# RAM_Module.net
KiCad netlist of a schematic drawn in Altium Designer
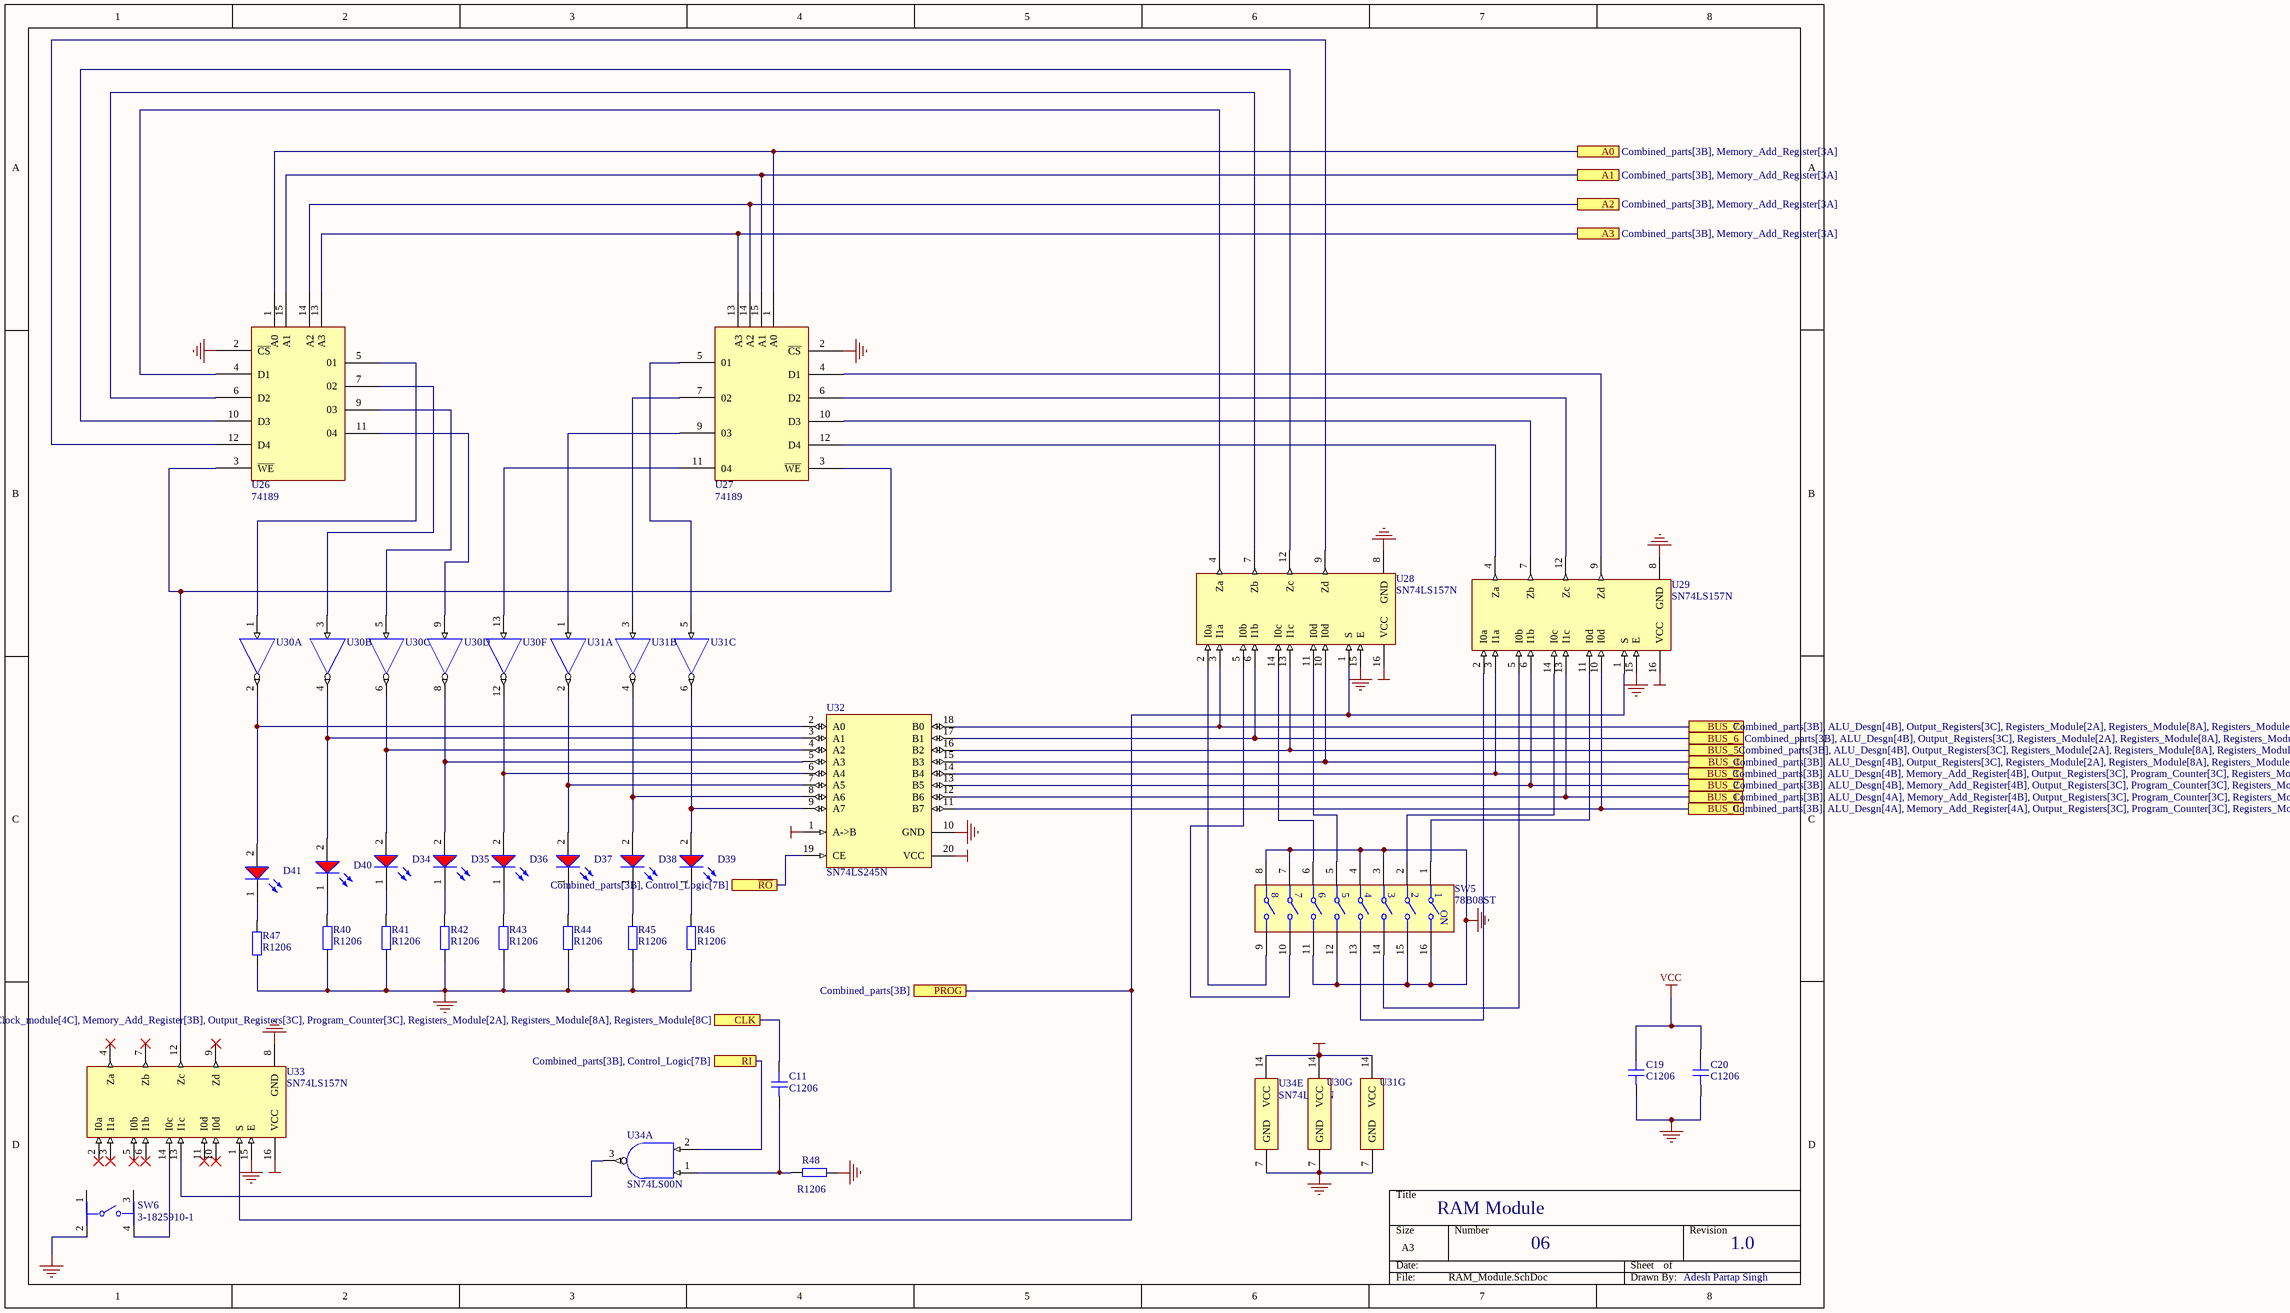
[diagram p0: RAM_Module.SchDoc]

(export (version "E")
  (design (tool "Eeschema 10.0.6"))
  (components
    (comp (ref "C11")
      (value "C1206")
      (footprint "CAP_1206")
      (description "Capacitor SMD 1206")
      (libsource (lib "Schematic-Lib-PhilsLab") (part "CAP_1206"))
    )
    (comp (ref "C19")
      (value "C1206")
      (footprint "CAP_1206")
      (description "Capacitor SMD 1206")
      (libsource (lib "Schematic-Lib-PhilsLab") (part "CAP_1206"))
    )
    (comp (ref "C20")
      (value "C1206")
      (footprint "CAP_1206")
      (description "Capacitor SMD 1206")
      (libsource (lib "Schematic-Lib-PhilsLab") (part "CAP_1206"))
    )
    (comp (ref "D34")
      (value "151053RS03000")
      (footprint "WL-TMRW_D5.8H11.7")
      (libsource (lib "8BIT_COMP_LIB") (part "CMP-1489-00007-2"))
    )
    (comp (ref "D35")
      (value "151053RS03000")
      (footprint "WL-TMRW_D5.8H11.7")
      (libsource (lib "8BIT_COMP_LIB") (part "CMP-1489-00007-2"))
    )
    (comp (ref "D36")
      (value "151053RS03000")
      (footprint "WL-TMRW_D5.8H11.7")
      (libsource (lib "8BIT_COMP_LIB") (part "CMP-1489-00007-2"))
    )
    (comp (ref "D37")
      (value "151053RS03000")
      (footprint "WL-TMRW_D5.8H11.7")
      (libsource (lib "8BIT_COMP_LIB") (part "CMP-1489-00007-2"))
    )
    (comp (ref "D38")
      (value "151053RS03000")
      (footprint "WL-TMRW_D5.8H11.7")
      (libsource (lib "8BIT_COMP_LIB") (part "CMP-1489-00007-2"))
    )
    (comp (ref "D39")
      (value "151053RS03000")
      (footprint "WL-TMRW_D5.8H11.7")
      (libsource (lib "8BIT_COMP_LIB") (part "CMP-1489-00007-2"))
    )
    (comp (ref "D40")
      (value "151053RS03000")
      (footprint "WL-TMRW_D5.8H11.7")
      (libsource (lib "8BIT_COMP_LIB") (part "CMP-1489-00007-2"))
    )
    (comp (ref "D41")
      (value "151053RS03000")
      (footprint "WL-TMRW_D5.8H11.7")
      (libsource (lib "8BIT_COMP_LIB") (part "CMP-1489-00007-2"))
    )
    (comp (ref "R40")
      (value "R1206")
      (footprint "RES_1206")
      (description "Resistor SMD 1206")
      (libsource (lib "Schematic-Lib-PhilsLab") (part "RES_1206"))
    )
    (comp (ref "R41")
      (value "R1206")
      (footprint "RES_1206")
      (description "Resistor SMD 1206")
      (libsource (lib "Schematic-Lib-PhilsLab") (part "RES_1206"))
    )
    (comp (ref "R42")
      (value "R1206")
      (footprint "RES_1206")
      (description "Resistor SMD 1206")
      (libsource (lib "Schematic-Lib-PhilsLab") (part "RES_1206"))
    )
    (comp (ref "R43")
      (value "R1206")
      (footprint "RES_1206")
      (description "Resistor SMD 1206")
      (libsource (lib "Schematic-Lib-PhilsLab") (part "RES_1206"))
    )
    (comp (ref "R44")
      (value "R1206")
      (footprint "RES_1206")
      (description "Resistor SMD 1206")
      (libsource (lib "Schematic-Lib-PhilsLab") (part "RES_1206"))
    )
    (comp (ref "R45")
      (value "R1206")
      (footprint "RES_1206")
      (description "Resistor SMD 1206")
      (libsource (lib "Schematic-Lib-PhilsLab") (part "RES_1206"))
    )
    (comp (ref "R46")
      (value "R1206")
      (footprint "RES_1206")
      (description "Resistor SMD 1206")
      (libsource (lib "Schematic-Lib-PhilsLab") (part "RES_1206"))
    )
    (comp (ref "R47")
      (value "R1206")
      (footprint "RES_1206")
      (description "Resistor SMD 1206")
      (libsource (lib "Schematic-Lib-PhilsLab") (part "RES_1206"))
    )
    (comp (ref "R48")
      (value "R1206")
      (footprint "RES_1206")
      (description "Resistor SMD 1206")
      (libsource (lib "Schematic-Lib-PhilsLab") (part "RES_1206"))
    )
    (comp (ref "SW5")
      (value "78B08ST")
      (footprint "FP-78B08ST-MFG")
      (description "SWITCH SLIDE DIP SPST 150MA 30V")
      (libsource (lib "8BIT_COMP_LIB") (part "CMP-31942-000004-2"))
    )
    (comp (ref "SW6")
      (value "3-1825910-1")
      (footprint "FP-3-1825910-1-MFG")
      (description "SWITCH TACTILE SPST-NO 0.05A 24V")
      (fields
        (field (name "MANUFACTURER") "TE Connectivity")
        (field (name "OCTOPART") "https://octopart.com/3-1825910-1-te+connectivity-46506874")
      )
      (libsource (lib "8BIT_COMP_LIB") (part "CMP-03407-000001-1"))
    )
    (comp (ref "U26")
      (value "74189")
      (footprint "N0016A")
      (description "RAM")
      (fields
        (field (name "MANUFACTURER") "Texas Instruments")
        (field (name "GENERIC PART NUMBER") "SN74LS157")
      )
      (libsource (lib "8BIT_COMP_LIB") (part "64 BIT RAM"))
    )
    (comp (ref "U27")
      (value "74189")
      (footprint "N0016A")
      (description "RAM")
      (fields
        (field (name "MANUFACTURER") "Texas Instruments")
        (field (name "GENERIC PART NUMBER") "SN74LS157")
      )
      (libsource (lib "8BIT_COMP_LIB") (part "64 BIT RAM_2"))
    )
    (comp (ref "U28")
      (value "SN74LS157N")
      (footprint "N0016A")
      (description "Quadruple 2-Line To 1-Line Data Selectors/Multiplexers, N0016A, TUBE")
      (fields
        (field (name "MANUFACTURER") "Texas Instruments")
        (field (name "GENERIC PART NUMBER") "SN74LS157")
      )
      (libsource (lib "8BIT_COMP_LIB") (part "CMP-1633-00683-2"))
    )
    (comp (ref "U29")
      (value "SN74LS157N")
      (footprint "N0016A")
      (description "Quadruple 2-Line To 1-Line Data Selectors/Multiplexers, N0016A, TUBE")
      (fields
        (field (name "MANUFACTURER") "Texas Instruments")
        (field (name "GENERIC PART NUMBER") "SN74LS157")
      )
      (libsource (lib "8BIT_COMP_LIB") (part "CMP-1633-00683-2"))
    )
    (comp (ref "U30")
      (value "SN74LS04NSR")
      (footprint "NS0014A_M")
      (description "Hex inverters, NS0014A, LARGE T&R")
      (fields
        (field (name "MANUFACTURER") "Texas Instruments")
        (field (name "GENERIC PART NUMBER") "SN74LS04")
      )
      (libsource (lib "8BIT_COMP_LIB") (part "CMP-1615-00958-3"))
    )
    (comp (ref "U31")
      (value "SN74LS04NSR")
      (footprint "NS0014A_M")
      (description "Hex inverters, NS0014A, LARGE T&R")
      (fields
        (field (name "MANUFACTURER") "Texas Instruments")
        (field (name "GENERIC PART NUMBER") "SN74LS04")
      )
      (libsource (lib "8BIT_COMP_LIB") (part "CMP-1615-00958-3"))
    )
    (comp (ref "U32")
      (value "SN74LS245N")
      (footprint "FP-N0020A-MFG")
      (description "IC TXRX NON-INVERT 5.25V 20DIP")
      (libsource (lib "8BIT_COMP_LIB") (part "CMP-1620-00419-3"))
    )
    (comp (ref "U33")
      (value "SN74LS157N")
      (footprint "N0016A")
      (description "Quadruple 2-Line To 1-Line Data Selectors/Multiplexers, N0016A, TUBE")
      (fields
        (field (name "MANUFACTURER") "Texas Instruments")
        (field (name "GENERIC PART NUMBER") "SN74LS157")
      )
      (libsource (lib "8BIT_COMP_LIB") (part "CMP-1633-00683-2"))
    )
    (comp (ref "U34")
      (value "SN74LS00N")
      (footprint "N0014A")
      (description "Quad 2-input positive-NAND gates, N0014A, TUBE")
      (fields
        (field (name "MANUFACTURER") "Texas Instruments")
        (field (name "GENERIC PART NUMBER") "SN74LS00")
      )
      (libsource (lib "") (part "CMP-1627-00476-2_1"))
    )
  )
  (nets
    (net (code "1") (name "/A0") (class "Default")
      (node (ref "U26") (pin "1") (pinfunction "A0_1") (pintype "passive"))
      (node (ref "U27") (pin "1") (pinfunction "A0_1") (pintype "passive"))
    )
    (net (code "2") (name "/A1") (class "Default")
      (node (ref "U26") (pin "15") (pinfunction "A1_15") (pintype "passive"))
      (node (ref "U27") (pin "15") (pinfunction "A1_15") (pintype "passive"))
    )
    (net (code "3") (name "/A2") (class "Default")
      (node (ref "U26") (pin "14") (pinfunction "A2_14") (pintype "passive"))
      (node (ref "U27") (pin "14") (pinfunction "A2_14") (pintype "passive"))
    )
    (net (code "4") (name "/A3") (class "Default")
      (node (ref "U26") (pin "13") (pinfunction "A3_13") (pintype "passive"))
      (node (ref "U27") (pin "13") (pinfunction "A3_13") (pintype "passive"))
    )
    (net (code "5") (name "/BUS_0") (class "Default")
      (node (ref "U29") (pin "10") (pinfunction "I0d_10") (pintype "input"))
      (node (ref "U32") (pin "11") (pinfunction "B7_11") (pintype "bidirectional"))
    )
    (net (code "6") (name "/BUS_1") (class "Default")
      (node (ref "U29") (pin "13") (pinfunction "I1c_13") (pintype "input"))
      (node (ref "U32") (pin "12") (pinfunction "B6_12") (pintype "bidirectional"))
    )
    (net (code "7") (name "/BUS_2") (class "Default")
      (node (ref "U29") (pin "6") (pinfunction "I1b_6") (pintype "input"))
      (node (ref "U32") (pin "13") (pinfunction "B5_13") (pintype "bidirectional"))
    )
    (net (code "8") (name "/BUS_3") (class "Default")
      (node (ref "U29") (pin "3") (pinfunction "I1a_3") (pintype "input"))
      (node (ref "U32") (pin "14") (pinfunction "B4_14") (pintype "bidirectional"))
    )
    (net (code "9") (name "/BUS_4") (class "Default")
      (node (ref "U28") (pin "10") (pinfunction "I0d_10") (pintype "input"))
      (node (ref "U32") (pin "15") (pinfunction "B3_15") (pintype "bidirectional"))
    )
    (net (code "10") (name "/BUS_5") (class "Default")
      (node (ref "U28") (pin "13") (pinfunction "I1c_13") (pintype "input"))
      (node (ref "U32") (pin "16") (pinfunction "B2_16") (pintype "bidirectional"))
    )
    (net (code "11") (name "/BUS_6") (class "Default")
      (node (ref "U28") (pin "6") (pinfunction "I1b_6") (pintype "input"))
      (node (ref "U32") (pin "17") (pinfunction "B1_17") (pintype "bidirectional"))
    )
    (net (code "12") (name "/BUS_7") (class "Default")
      (node (ref "U28") (pin "3") (pinfunction "I1a_3") (pintype "input"))
      (node (ref "U32") (pin "18") (pinfunction "B0_18") (pintype "bidirectional"))
    )
    (net (code "13") (name "/CLK") (class "Default")
      (node (ref "C11") (pin "2") (pinfunction "2_2") (pintype "passive"))
    )
    (net (code "14") (name "/PROG") (class "Default")
      (node (ref "U28") (pin "1") (pinfunction "S_1") (pintype "input"))
      (node (ref "U29") (pin "1") (pinfunction "S_1") (pintype "input"))
      (node (ref "U33") (pin "1") (pinfunction "S_1") (pintype "input"))
    )
    (net (code "15") (name "/RI") (class "Default")
      (node (ref "U34") (pin "2") (pinfunction "1B_2") (pintype "input"))
    )
    (net (code "16") (name "/~{RO}") (class "Default")
      (node (ref "U32") (pin "19") (pinfunction "CE_19") (pintype "input"))
    )
    (net (code "17") (name "GND") (class "Default")
      (node (ref "C19") (pin "1") (pinfunction "1_1") (pintype "passive"))
      (node (ref "C20") (pin "1") (pinfunction "1_1") (pintype "passive"))
      (node (ref "R40") (pin "1") (pinfunction "1_1") (pintype "passive"))
      (node (ref "R41") (pin "1") (pinfunction "1_1") (pintype "passive"))
      (node (ref "R42") (pin "1") (pinfunction "1_1") (pintype "passive"))
      (node (ref "R43") (pin "1") (pinfunction "1_1") (pintype "passive"))
      (node (ref "R44") (pin "1") (pinfunction "1_1") (pintype "passive"))
      (node (ref "R45") (pin "1") (pinfunction "1_1") (pintype "passive"))
      (node (ref "R46") (pin "1") (pinfunction "1_1") (pintype "passive"))
      (node (ref "R47") (pin "1") (pinfunction "1_1") (pintype "passive"))
      (node (ref "R48") (pin "1") (pinfunction "1_1") (pintype "passive"))
      (node (ref "SW5") (pin "11") (pinfunction "11_11") (pintype "passive"))
      (node (ref "SW5") (pin "12") (pinfunction "12_12") (pintype "passive"))
      (node (ref "SW5") (pin "15") (pinfunction "15_15") (pintype "passive"))
      (node (ref "SW5") (pin "16") (pinfunction "16_16") (pintype "passive"))
      (node (ref "SW5") (pin "3") (pinfunction "3_3") (pintype "passive"))
      (node (ref "SW5") (pin "4") (pinfunction "4_4") (pintype "passive"))
      (node (ref "SW5") (pin "7") (pinfunction "7_7") (pintype "passive"))
      (node (ref "SW5") (pin "8") (pinfunction "8_8") (pintype "passive"))
      (node (ref "SW6") (pin "2") (pinfunction "2_2") (pintype "passive"))
      (node (ref "U26") (pin "2") (pinfunction "~{CS}_2") (pintype "passive"))
      (node (ref "U27") (pin "2") (pinfunction "~{CS}_2") (pintype "passive"))
      (node (ref "U28") (pin "15") (pinfunction "E_15") (pintype "input"))
      (node (ref "U28") (pin "8") (pinfunction "GND_8") (pintype "power_in"))
      (node (ref "U29") (pin "15") (pinfunction "E_15") (pintype "input"))
      (node (ref "U29") (pin "8") (pinfunction "GND_8") (pintype "power_in"))
      (node (ref "U30") (pin "7") (pinfunction "GND_7") (pintype "power_in"))
      (node (ref "U31") (pin "7") (pinfunction "GND_7") (pintype "power_in"))
      (node (ref "U32") (pin "10") (pinfunction "GND_10") (pintype "power_in"))
      (node (ref "U33") (pin "15") (pinfunction "E_15") (pintype "input"))
      (node (ref "U33") (pin "8") (pinfunction "GND_8") (pintype "power_in"))
      (node (ref "U34") (pin "7") (pinfunction "GND_7") (pintype "power_in"))
    )
    (net (code "18") (name "Net-(D34-A)") (class "Default")
      (node (ref "D34") (pin "2") (pinfunction "A_2") (pintype "passive"))
      (node (ref "U30") (pin "6") (pinfunction "~{3Y}_6") (pintype "output"))
      (node (ref "U32") (pin "4") (pinfunction "A2_4") (pintype "bidirectional"))
    )
    (net (code "19") (name "Net-(D34-K)") (class "Default")
      (node (ref "D34") (pin "1") (pinfunction "K_1") (pintype "passive"))
      (node (ref "R41") (pin "2") (pinfunction "2_2") (pintype "passive"))
    )
    (net (code "20") (name "Net-(D35-A)") (class "Default")
      (node (ref "D35") (pin "2") (pinfunction "A_2") (pintype "passive"))
      (node (ref "U30") (pin "8") (pinfunction "~{4Y}_8") (pintype "output"))
      (node (ref "U32") (pin "5") (pinfunction "A3_5") (pintype "bidirectional"))
    )
    (net (code "21") (name "Net-(D35-K)") (class "Default")
      (node (ref "D35") (pin "1") (pinfunction "K_1") (pintype "passive"))
      (node (ref "R42") (pin "2") (pinfunction "2_2") (pintype "passive"))
    )
    (net (code "22") (name "Net-(D36-A)") (class "Default")
      (node (ref "D36") (pin "2") (pinfunction "A_2") (pintype "passive"))
      (node (ref "U30") (pin "12") (pinfunction "~{6Y}_12") (pintype "output"))
      (node (ref "U32") (pin "6") (pinfunction "A4_6") (pintype "bidirectional"))
    )
    (net (code "23") (name "Net-(D36-K)") (class "Default")
      (node (ref "D36") (pin "1") (pinfunction "K_1") (pintype "passive"))
      (node (ref "R43") (pin "2") (pinfunction "2_2") (pintype "passive"))
    )
    (net (code "24") (name "Net-(D37-A)") (class "Default")
      (node (ref "D37") (pin "2") (pinfunction "A_2") (pintype "passive"))
      (node (ref "U31") (pin "2") (pinfunction "~{1Y}_2") (pintype "output"))
      (node (ref "U32") (pin "7") (pinfunction "A5_7") (pintype "bidirectional"))
    )
    (net (code "25") (name "Net-(D37-K)") (class "Default")
      (node (ref "D37") (pin "1") (pinfunction "K_1") (pintype "passive"))
      (node (ref "R44") (pin "2") (pinfunction "2_2") (pintype "passive"))
    )
    (net (code "26") (name "Net-(D38-A)") (class "Default")
      (node (ref "D38") (pin "2") (pinfunction "A_2") (pintype "passive"))
      (node (ref "U31") (pin "4") (pinfunction "~{2Y}_4") (pintype "output"))
      (node (ref "U32") (pin "8") (pinfunction "A6_8") (pintype "bidirectional"))
    )
    (net (code "27") (name "Net-(D38-K)") (class "Default")
      (node (ref "D38") (pin "1") (pinfunction "K_1") (pintype "passive"))
      (node (ref "R45") (pin "2") (pinfunction "2_2") (pintype "passive"))
    )
    (net (code "28") (name "Net-(D39-A)") (class "Default")
      (node (ref "D39") (pin "2") (pinfunction "A_2") (pintype "passive"))
      (node (ref "U31") (pin "6") (pinfunction "~{3Y}_6") (pintype "output"))
      (node (ref "U32") (pin "9") (pinfunction "A7_9") (pintype "bidirectional"))
    )
    (net (code "29") (name "Net-(D39-K)") (class "Default")
      (node (ref "D39") (pin "1") (pinfunction "K_1") (pintype "passive"))
      (node (ref "R46") (pin "2") (pinfunction "2_2") (pintype "passive"))
    )
    (net (code "30") (name "Net-(D40-A)") (class "Default")
      (node (ref "D40") (pin "2") (pinfunction "A_2") (pintype "passive"))
      (node (ref "U30") (pin "4") (pinfunction "~{2Y}_4") (pintype "output"))
      (node (ref "U32") (pin "3") (pinfunction "A1_3") (pintype "bidirectional"))
    )
    (net (code "31") (name "Net-(D40-K)") (class "Default")
      (node (ref "D40") (pin "1") (pinfunction "K_1") (pintype "passive"))
      (node (ref "R40") (pin "2") (pinfunction "2_2") (pintype "passive"))
    )
    (net (code "32") (name "Net-(D41-A)") (class "Default")
      (node (ref "D41") (pin "2") (pinfunction "A_2") (pintype "passive"))
      (node (ref "U30") (pin "2") (pinfunction "~{1Y}_2") (pintype "output"))
      (node (ref "U32") (pin "2") (pinfunction "A0_2") (pintype "bidirectional"))
    )
    (net (code "33") (name "Net-(D41-K)") (class "Default")
      (node (ref "D41") (pin "1") (pinfunction "K_1") (pintype "passive"))
      (node (ref "R47") (pin "2") (pinfunction "2_2") (pintype "passive"))
    )
    (net (code "34") (name "Net-(SW5-Pad1)") (class "Default")
      (node (ref "SW5") (pin "1") (pinfunction "1_1") (pintype "passive"))
      (node (ref "U29") (pin "11") (pinfunction "I0d_11") (pintype "input"))
    )
    (net (code "35") (name "Net-(SW5-Pad5)") (class "Default")
      (node (ref "SW5") (pin "5") (pinfunction "5_5") (pintype "passive"))
      (node (ref "U28") (pin "11") (pinfunction "I0d_11") (pintype "input"))
    )
    (net (code "36") (name "Net-(U26-01)") (class "Default")
      (node (ref "U26") (pin "5") (pinfunction "01_5") (pintype "passive"))
      (node (ref "U30") (pin "1") (pinfunction "1A_1") (pintype "input"))
    )
    (net (code "37") (name "Net-(U26-02)") (class "Default")
      (node (ref "U26") (pin "7") (pinfunction "02_7") (pintype "passive"))
      (node (ref "U30") (pin "3") (pinfunction "2A_3") (pintype "input"))
    )
    (net (code "38") (name "Net-(U26-03)") (class "Default")
      (node (ref "U26") (pin "9") (pinfunction "03_9") (pintype "passive"))
      (node (ref "U30") (pin "5") (pinfunction "3A_5") (pintype "input"))
    )
    (net (code "39") (name "Net-(U26-04)") (class "Default")
      (node (ref "U26") (pin "11") (pinfunction "04_11") (pintype "passive"))
      (node (ref "U30") (pin "9") (pinfunction "4A_9") (pintype "input"))
    )
    (net (code "40") (name "Net-(U26-D1)") (class "Default")
      (node (ref "U26") (pin "4") (pinfunction "D1_4") (pintype "passive"))
      (node (ref "U28") (pin "4") (pinfunction "Za_4") (pintype "output"))
    )
    (net (code "41") (name "Net-(U26-D2)") (class "Default")
      (node (ref "U26") (pin "6") (pinfunction "D2_6") (pintype "passive"))
      (node (ref "U28") (pin "7") (pinfunction "Zb_7") (pintype "output"))
    )
    (net (code "42") (name "Net-(U26-D3)") (class "Default")
      (node (ref "U26") (pin "10") (pinfunction "D3_10") (pintype "passive"))
      (node (ref "U28") (pin "12") (pinfunction "Zc_12") (pintype "output"))
    )
    (net (code "43") (name "Net-(U26-D4)") (class "Default")
      (node (ref "U26") (pin "12") (pinfunction "D4_12") (pintype "passive"))
      (node (ref "U28") (pin "9") (pinfunction "Zd_9") (pintype "output"))
    )
    (net (code "44") (name "Net-(U26-~{WE})") (class "Default")
      (node (ref "U26") (pin "3") (pinfunction "~{WE}_3") (pintype "passive"))
      (node (ref "U27") (pin "3") (pinfunction "~{WE}_3") (pintype "passive"))
      (node (ref "U33") (pin "12") (pinfunction "Zc_12") (pintype "output"))
    )
    (net (code "45") (name "Net-(U27-01)") (class "Default")
      (node (ref "U27") (pin "5") (pinfunction "01_5") (pintype "passive"))
      (node (ref "U31") (pin "5") (pinfunction "3A_5") (pintype "input"))
    )
    (net (code "46") (name "Net-(U27-02)") (class "Default")
      (node (ref "U27") (pin "7") (pinfunction "02_7") (pintype "passive"))
      (node (ref "U31") (pin "3") (pinfunction "2A_3") (pintype "input"))
    )
    (net (code "47") (name "Net-(U27-03)") (class "Default")
      (node (ref "U27") (pin "9") (pinfunction "03_9") (pintype "passive"))
      (node (ref "U31") (pin "1") (pinfunction "1A_1") (pintype "input"))
    )
    (net (code "48") (name "Net-(U27-04)") (class "Default")
      (node (ref "U27") (pin "11") (pinfunction "04_11") (pintype "passive"))
      (node (ref "U30") (pin "13") (pinfunction "6A_13") (pintype "input"))
    )
    (net (code "49") (name "Net-(U27-D1)") (class "Default")
      (node (ref "U27") (pin "4") (pinfunction "D1_4") (pintype "passive"))
      (node (ref "U29") (pin "9") (pinfunction "Zd_9") (pintype "output"))
    )
    (net (code "50") (name "Net-(U27-D2)") (class "Default")
      (node (ref "U27") (pin "6") (pinfunction "D2_6") (pintype "passive"))
      (node (ref "U29") (pin "12") (pinfunction "Zc_12") (pintype "output"))
    )
    (net (code "51") (name "Net-(U27-D3)") (class "Default")
      (node (ref "U27") (pin "10") (pinfunction "D3_10") (pintype "passive"))
      (node (ref "U29") (pin "7") (pinfunction "Zb_7") (pintype "output"))
    )
    (net (code "52") (name "Net-(U27-D4)") (class "Default")
      (node (ref "U27") (pin "12") (pinfunction "D4_12") (pintype "passive"))
      (node (ref "U29") (pin "4") (pinfunction "Za_4") (pintype "output"))
    )
    (net (code "53") (name "Net-(U28-I0a)") (class "Default")
      (node (ref "SW5") (pin "9") (pinfunction "9_9") (pintype "passive"))
      (node (ref "U28") (pin "2") (pinfunction "I0a_2") (pintype "input"))
    )
    (net (code "54") (name "Net-(U28-I0b)") (class "Default")
      (node (ref "SW5") (pin "10") (pinfunction "10_10") (pintype "passive"))
      (node (ref "U28") (pin "5") (pinfunction "I0b_5") (pintype "input"))
    )
    (net (code "55") (name "Net-(U28-I0c)") (class "Default")
      (node (ref "SW5") (pin "6") (pinfunction "6_6") (pintype "passive"))
      (node (ref "U28") (pin "14") (pinfunction "I0c_14") (pintype "input"))
    )
    (net (code "56") (name "Net-(U29-I0a)") (class "Default")
      (node (ref "SW5") (pin "13") (pinfunction "13_13") (pintype "passive"))
      (node (ref "U29") (pin "2") (pinfunction "I0a_2") (pintype "input"))
    )
    (net (code "57") (name "Net-(U29-I0b)") (class "Default")
      (node (ref "SW5") (pin "14") (pinfunction "14_14") (pintype "passive"))
      (node (ref "U29") (pin "5") (pinfunction "I0b_5") (pintype "input"))
    )
    (net (code "58") (name "Net-(U29-I0c)") (class "Default")
      (node (ref "SW5") (pin "2") (pinfunction "2_2") (pintype "passive"))
      (node (ref "U29") (pin "14") (pinfunction "I0c_14") (pintype "input"))
    )
    (net (code "59") (name "Net-(U33-I0c)") (class "Default")
      (node (ref "SW6") (pin "4") (pinfunction "4_4") (pintype "passive"))
      (node (ref "U33") (pin "14") (pinfunction "I0c_14") (pintype "input"))
    )
    (net (code "60") (name "Net-(U33-I1c)") (class "Default")
      (node (ref "U33") (pin "13") (pinfunction "I1c_13") (pintype "input"))
      (node (ref "U34") (pin "3") (pinfunction "1Y_3") (pintype "output"))
    )
    (net (code "61") (name "Net-(U34A-1A)") (class "Default")
      (node (ref "C11") (pin "1") (pinfunction "1_1") (pintype "passive"))
      (node (ref "R48") (pin "2") (pinfunction "2_2") (pintype "passive"))
      (node (ref "U34") (pin "1") (pinfunction "1A_1") (pintype "input"))
    )
    (net (code "62") (name "VCC") (class "Default")
      (node (ref "C19") (pin "2") (pinfunction "2_2") (pintype "passive"))
      (node (ref "C20") (pin "2") (pinfunction "2_2") (pintype "passive"))
      (node (ref "U28") (pin "16") (pinfunction "VCC_16") (pintype "power_in"))
      (node (ref "U29") (pin "16") (pinfunction "VCC_16") (pintype "power_in"))
      (node (ref "U30") (pin "14") (pinfunction "VCC_14") (pintype "power_in"))
      (node (ref "U31") (pin "14") (pinfunction "VCC_14") (pintype "power_in"))
      (node (ref "U32") (pin "1") (pinfunction "A->B_1") (pintype "input"))
      (node (ref "U32") (pin "20") (pinfunction "VCC_20") (pintype "power_in"))
      (node (ref "U33") (pin "16") (pinfunction "VCC_16") (pintype "power_in"))
      (node (ref "U34") (pin "14") (pinfunction "VCC_14") (pintype "power_in"))
    )
    (net (code "63") (name "unconnected-(SW6-Pad1)") (class "Default")
      (node (ref "SW6") (pin "1") (pinfunction "1_1") (pintype "passive"))
    )
    (net (code "64") (name "unconnected-(SW6-Pad3)") (class "Default")
      (node (ref "SW6") (pin "3") (pinfunction "3_3") (pintype "passive"))
    )
    (net (code "65") (name "unconnected-(U33-I0a-Pad2)") (class "Default")
      (node (ref "U33") (pin "2") (pinfunction "I0a_2") (pintype "input+no_connect"))
    )
    (net (code "66") (name "unconnected-(U33-I0b-Pad5)") (class "Default")
      (node (ref "U33") (pin "5") (pinfunction "I0b_5") (pintype "input+no_connect"))
    )
    (net (code "67") (name "unconnected-(U33-I0d-Pad10)") (class "Default")
      (node (ref "U33") (pin "10") (pinfunction "I0d_10") (pintype "input+no_connect"))
    )
    (net (code "68") (name "unconnected-(U33-I0d-Pad11)") (class "Default")
      (node (ref "U33") (pin "11") (pinfunction "I0d_11") (pintype "input+no_connect"))
    )
    (net (code "69") (name "unconnected-(U33-I1a-Pad3)") (class "Default")
      (node (ref "U33") (pin "3") (pinfunction "I1a_3") (pintype "input+no_connect"))
    )
    (net (code "70") (name "unconnected-(U33-I1b-Pad6)") (class "Default")
      (node (ref "U33") (pin "6") (pinfunction "I1b_6") (pintype "input+no_connect"))
    )
    (net (code "71") (name "unconnected-(U33-Za-Pad4)") (class "Default")
      (node (ref "U33") (pin "4") (pinfunction "Za_4") (pintype "output+no_connect"))
    )
    (net (code "72") (name "unconnected-(U33-Zb-Pad7)") (class "Default")
      (node (ref "U33") (pin "7") (pinfunction "Zb_7") (pintype "output+no_connect"))
    )
    (net (code "73") (name "unconnected-(U33-Zd-Pad9)") (class "Default")
      (node (ref "U33") (pin "9") (pinfunction "Zd_9") (pintype "output+no_connect"))
    )
  )
)
